# with-vreg.net
KiCad netlist of a schematic drawn in EAGLE
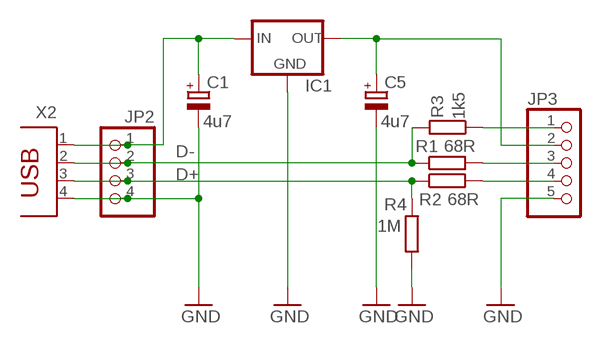
[diagram p0: schematic, sheet 1]

(export (version "E")
  (design (tool "Eeschema 10.0.6"))
  (components
    (comp (ref "C1")
      (value "4u7")
      (footprint "eagle-import:E2-5")
      (libsource (lib "eagle-import") (part "CPOL-EUE2-5"))
    )
    (comp (ref "C5")
      (value "4u7")
      (footprint "eagle-import:E2-5")
      (libsource (lib "eagle-import") (part "CPOL-EUE2-5"))
    )
    (comp (ref "IC1")
      (value "V_REG_78XXSINK")
      (footprint "eagle-import:TO220-IGO")
      (libsource (lib "eagle-import") (part "V_REG_78XXSINK"))
    )
    (comp (ref "JP2")
      (value "PINHD-1X4")
      (footprint "eagle-import:1X04")
      (libsource (lib "eagle-import") (part "PINHD-1X4"))
    )
    (comp (ref "JP3")
      (value "PINHD-1X5")
      (footprint "eagle-import:1X05")
      (libsource (lib "eagle-import") (part "PINHD-1X5"))
    )
    (comp (ref "R1")
      (value "68R")
      (footprint "eagle-import:0207_10")
      (libsource (lib "eagle-import") (part "R-EU_0207/10"))
    )
    (comp (ref "R2")
      (value "68R")
      (footprint "eagle-import:0207_10")
      (libsource (lib "eagle-import") (part "R-EU_0207/10"))
    )
    (comp (ref "R3")
      (value "1k5")
      (footprint "eagle-import:0207_10")
      (libsource (lib "eagle-import") (part "R-EU_0207/10"))
    )
    (comp (ref "R4")
      (value "1M")
      (footprint "eagle-import:0207_10")
      (libsource (lib "eagle-import") (part "R-EU_0207/10"))
    )
    (comp (ref "X2")
      (value "PN61729")
      (footprint "eagle-import:PN61729")
      (libsource (lib "eagle-import") (part "PN61729"))
    )
  )
  (nets
    (net (code "1") (name "/D+") (class "Default")
      (node (ref "JP2") (pin "3") (pinfunction "3_3") (pintype "passive"))
      (node (ref "R2") (pin "1") (pinfunction "1_1") (pintype "passive"))
      (node (ref "R4") (pin "2") (pinfunction "2_2") (pintype "passive"))
      (node (ref "X2") (pin "3") (pinfunction "3_3") (pintype "bidirectional"))
    )
    (net (code "2") (name "/D-") (class "Default")
      (node (ref "JP2") (pin "2") (pinfunction "2_2") (pintype "passive"))
      (node (ref "R1") (pin "1") (pinfunction "1_1") (pintype "passive"))
      (node (ref "R3") (pin "2") (pinfunction "2_2") (pintype "passive"))
      (node (ref "X2") (pin "2") (pinfunction "2_2") (pintype "bidirectional"))
    )
    (net (code "3") (name "GND") (class "Default")
      (node (ref "C1") (pin "-") (pinfunction "-_-") (pintype "passive"))
      (node (ref "C5") (pin "-") (pinfunction "-_-") (pintype "passive"))
      (node (ref "IC1") (pin "GND") (pinfunction "GND_GND") (pintype "input"))
      (node (ref "JP2") (pin "4") (pinfunction "4_4") (pintype "passive"))
      (node (ref "JP3") (pin "5") (pinfunction "5_5") (pintype "passive"))
      (node (ref "R4") (pin "1") (pinfunction "1_1") (pintype "passive"))
      (node (ref "X2") (pin "4") (pinfunction "4_4") (pintype "bidirectional"))
    )
    (net (code "4") (name "Net-(C1-Pad+)") (class "Default")
      (node (ref "C1") (pin "+") (pinfunction "+_+") (pintype "passive"))
      (node (ref "IC1") (pin "IN") (pinfunction "IN_IN") (pintype "input"))
      (node (ref "JP2") (pin "1") (pinfunction "1_1") (pintype "passive"))
      (node (ref "X2") (pin "1") (pinfunction "1_1") (pintype "bidirectional"))
    )
    (net (code "5") (name "Net-(C5-Pad+)") (class "Default")
      (node (ref "C5") (pin "+") (pinfunction "+_+") (pintype "passive"))
      (node (ref "IC1") (pin "OUT") (pinfunction "OUT_OUT") (pintype "output"))
      (node (ref "JP3") (pin "2") (pinfunction "2_2") (pintype "passive"))
    )
    (net (code "6") (name "Net-(JP3-Pad1)") (class "Default")
      (node (ref "JP3") (pin "1") (pinfunction "1_1") (pintype "passive"))
      (node (ref "R3") (pin "1") (pinfunction "1_1") (pintype "passive"))
    )
    (net (code "7") (name "Net-(JP3-Pad3)") (class "Default")
      (node (ref "JP3") (pin "3") (pinfunction "3_3") (pintype "passive"))
      (node (ref "R1") (pin "2") (pinfunction "2_2") (pintype "passive"))
    )
    (net (code "8") (name "Net-(JP3-Pad4)") (class "Default")
      (node (ref "JP3") (pin "4") (pinfunction "4_4") (pintype "passive"))
      (node (ref "R2") (pin "2") (pinfunction "2_2") (pintype "passive"))
    )
  )
)
